# MCU.net
KiCad netlist of a schematic drawn in Altium Designer
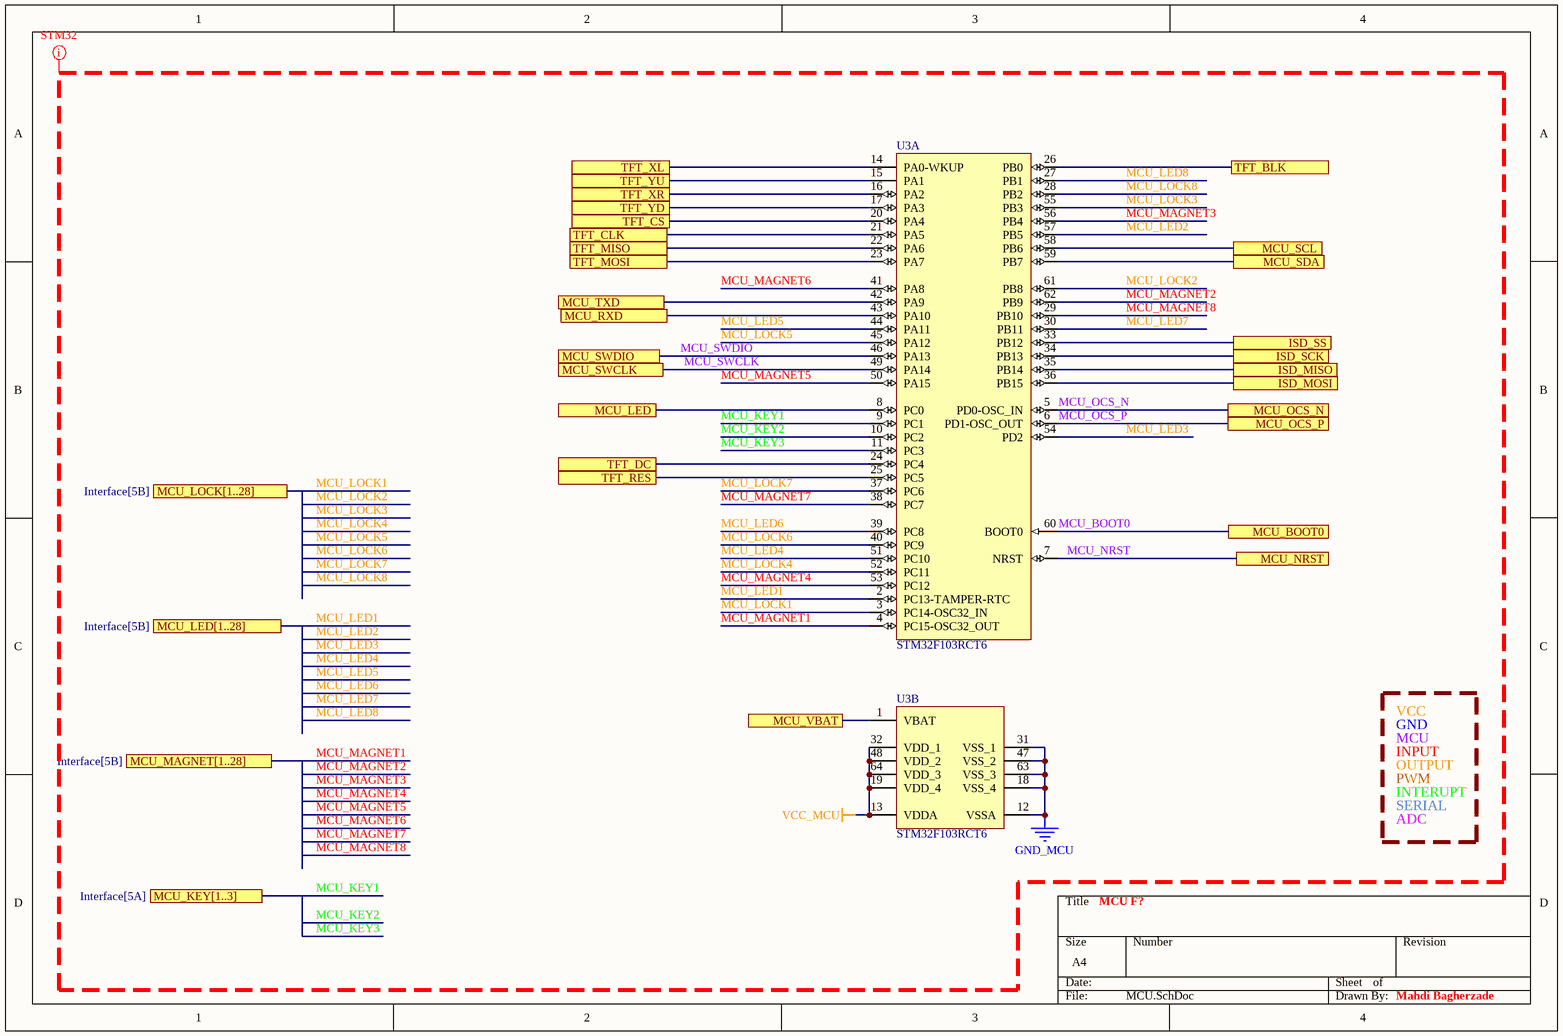
[diagram p0: MCU.SchDoc]

(export (version "E")
  (design (tool "Eeschema 10.0.6"))
  (components
    (comp (ref "U3")
      (value "STM32F103RCT6")
      (footprint "STM-LQFP64_N")
      (libsource (lib "ST Microelectronics STM32 F1") (part "STM32F103RCT6"))
    )
  )
  (nets
    (net (code "61") (name "/ISD_MISO") (class "Default")
      (node (ref "U3") (pin "35") (pinfunction "PB14_35") (pintype "bidirectional"))
    )
    (net (code "62") (name "/ISD_MOSI") (class "Default")
      (node (ref "U3") (pin "36") (pinfunction "PB15_36") (pintype "bidirectional"))
    )
    (net (code "63") (name "/ISD_SCK") (class "Default")
      (node (ref "U3") (pin "34") (pinfunction "PB13_34") (pintype "bidirectional"))
    )
    (net (code "64") (name "/ISD_SS") (class "Default")
      (node (ref "U3") (pin "33") (pinfunction "PB12_33") (pintype "bidirectional"))
    )
    (net (code "65") (name "/MCU_BOOT0") (class "Default")
      (node (ref "U3") (pin "60") (pinfunction "BOOT0_60") (pintype "input"))
    )
    (net (code "66") (name "/MCU_KEY1") (class "Default")
      (node (ref "U3") (pin "9") (pinfunction "PC1_9") (pintype "bidirectional"))
    )
    (net (code "67") (name "/MCU_KEY2") (class "Default")
      (node (ref "U3") (pin "10") (pinfunction "PC2_10") (pintype "bidirectional"))
    )
    (net (code "68") (name "/MCU_KEY3") (class "Default")
      (node (ref "U3") (pin "11") (pinfunction "PC3_11") (pintype "bidirectional"))
    )
    (net (code "70") (name "/MCU_LED") (class "Default")
      (node (ref "U3") (pin "8") (pinfunction "PC0_8") (pintype "bidirectional"))
    )
    (net (code "71") (name "/MCU_LED1") (class "Default")
      (node (ref "U3") (pin "2") (pinfunction "PC13-TAMPER-RTC_2") (pintype "bidirectional"))
    )
    (net (code "72") (name "/MCU_LED2") (class "Default")
      (node (ref "U3") (pin "57") (pinfunction "PB5_57") (pintype "bidirectional"))
    )
    (net (code "73") (name "/MCU_LED3") (class "Default")
      (node (ref "U3") (pin "54") (pinfunction "PD2_54") (pintype "bidirectional"))
    )
    (net (code "74") (name "/MCU_LED4") (class "Default")
      (node (ref "U3") (pin "51") (pinfunction "PC10_51") (pintype "bidirectional"))
    )
    (net (code "75") (name "/MCU_LED5") (class "Default")
      (node (ref "U3") (pin "44") (pinfunction "PA11_44") (pintype "bidirectional"))
    )
    (net (code "76") (name "/MCU_LED6") (class "Default")
      (node (ref "U3") (pin "39") (pinfunction "PC8_39") (pintype "bidirectional"))
    )
    (net (code "77") (name "/MCU_LED7") (class "Default")
      (node (ref "U3") (pin "30") (pinfunction "PB11_30") (pintype "bidirectional"))
    )
    (net (code "78") (name "/MCU_LED8") (class "Default")
      (node (ref "U3") (pin "27") (pinfunction "PB1_27") (pintype "bidirectional"))
    )
    (net (code "80") (name "/MCU_LOCK1") (class "Default")
      (node (ref "U3") (pin "3") (pinfunction "PC14-OSC32_IN_3") (pintype "bidirectional"))
    )
    (net (code "81") (name "/MCU_LOCK2") (class "Default")
      (node (ref "U3") (pin "61") (pinfunction "PB8_61") (pintype "bidirectional"))
    )
    (net (code "82") (name "/MCU_LOCK3") (class "Default")
      (node (ref "U3") (pin "55") (pinfunction "PB3_55") (pintype "bidirectional"))
    )
    (net (code "83") (name "/MCU_LOCK4") (class "Default")
      (node (ref "U3") (pin "52") (pinfunction "PC11_52") (pintype "bidirectional"))
    )
    (net (code "84") (name "/MCU_LOCK5") (class "Default")
      (node (ref "U3") (pin "45") (pinfunction "PA12_45") (pintype "bidirectional"))
    )
    (net (code "85") (name "/MCU_LOCK6") (class "Default")
      (node (ref "U3") (pin "40") (pinfunction "PC9_40") (pintype "bidirectional"))
    )
    (net (code "86") (name "/MCU_LOCK7") (class "Default")
      (node (ref "U3") (pin "37") (pinfunction "PC6_37") (pintype "bidirectional"))
    )
    (net (code "87") (name "/MCU_LOCK8") (class "Default")
      (node (ref "U3") (pin "28") (pinfunction "PB2_28") (pintype "bidirectional"))
    )
    (net (code "89") (name "/MCU_MAGNET1") (class "Default")
      (node (ref "U3") (pin "4") (pinfunction "PC15-OSC32_OUT_4") (pintype "bidirectional"))
    )
    (net (code "90") (name "/MCU_MAGNET2") (class "Default")
      (node (ref "U3") (pin "62") (pinfunction "PB9_62") (pintype "bidirectional"))
    )
    (net (code "91") (name "/MCU_MAGNET3") (class "Default")
      (node (ref "U3") (pin "56") (pinfunction "PB4_56") (pintype "bidirectional"))
    )
    (net (code "92") (name "/MCU_MAGNET4") (class "Default")
      (node (ref "U3") (pin "53") (pinfunction "PC12_53") (pintype "bidirectional"))
    )
    (net (code "93") (name "/MCU_MAGNET5") (class "Default")
      (node (ref "U3") (pin "50") (pinfunction "PA15_50") (pintype "bidirectional"))
    )
    (net (code "94") (name "/MCU_MAGNET6") (class "Default")
      (node (ref "U3") (pin "41") (pinfunction "PA8_41") (pintype "bidirectional"))
    )
    (net (code "95") (name "/MCU_MAGNET7") (class "Default")
      (node (ref "U3") (pin "38") (pinfunction "PC7_38") (pintype "bidirectional"))
    )
    (net (code "96") (name "/MCU_MAGNET8") (class "Default")
      (node (ref "U3") (pin "29") (pinfunction "PB10_29") (pintype "bidirectional"))
    )
    (net (code "98") (name "/MCU_NRST") (class "Default")
      (node (ref "U3") (pin "7") (pinfunction "NRST_7") (pintype "bidirectional"))
    )
    (net (code "99") (name "/MCU_OCS_N") (class "Default")
      (node (ref "U3") (pin "5") (pinfunction "PD0-OSC_IN_5") (pintype "bidirectional"))
    )
    (net (code "100") (name "/MCU_OCS_P") (class "Default")
      (node (ref "U3") (pin "6") (pinfunction "PD1-OSC_OUT_6") (pintype "bidirectional"))
    )
    (net (code "101") (name "/MCU_RXD") (class "Default")
      (node (ref "U3") (pin "43") (pinfunction "PA10_43") (pintype "bidirectional"))
    )
    (net (code "102") (name "/MCU_SCL") (class "Default")
      (node (ref "U3") (pin "58") (pinfunction "PB6_58") (pintype "bidirectional"))
    )
    (net (code "103") (name "/MCU_SDA") (class "Default")
      (node (ref "U3") (pin "59") (pinfunction "PB7_59") (pintype "bidirectional"))
    )
    (net (code "104") (name "/MCU_SWCLK") (class "Default")
      (node (ref "U3") (pin "49") (pinfunction "PA14_49") (pintype "bidirectional"))
    )
    (net (code "105") (name "/MCU_SWDIO") (class "Default")
      (node (ref "U3") (pin "46") (pinfunction "PA13_46") (pintype "bidirectional"))
    )
    (net (code "106") (name "/MCU_TXD") (class "Default")
      (node (ref "U3") (pin "42") (pinfunction "PA9_42") (pintype "bidirectional"))
    )
    (net (code "107") (name "/MCU_VBAT") (class "Default")
      (node (ref "U3") (pin "1") (pinfunction "VBAT_1") (pintype "power_in"))
    )
    (net (code "108") (name "/TFT_BLK") (class "Default")
      (node (ref "U3") (pin "26") (pinfunction "PB0_26") (pintype "bidirectional"))
    )
    (net (code "109") (name "/TFT_CLK") (class "Default")
      (node (ref "U3") (pin "21") (pinfunction "PA5_21") (pintype "bidirectional"))
    )
    (net (code "110") (name "/TFT_CS") (class "Default")
      (node (ref "U3") (pin "20") (pinfunction "PA4_20") (pintype "bidirectional"))
    )
    (net (code "111") (name "/TFT_DC") (class "Default")
      (node (ref "U3") (pin "24") (pinfunction "PC4_24") (pintype "bidirectional"))
    )
    (net (code "112") (name "/TFT_MISO") (class "Default")
      (node (ref "U3") (pin "22") (pinfunction "PA6_22") (pintype "bidirectional"))
    )
    (net (code "113") (name "/TFT_MOSI") (class "Default")
      (node (ref "U3") (pin "23") (pinfunction "PA7_23") (pintype "bidirectional"))
    )
    (net (code "114") (name "/TFT_RES") (class "Default")
      (node (ref "U3") (pin "25") (pinfunction "PC5_25") (pintype "bidirectional"))
    )
    (net (code "115") (name "/TFT_XL") (class "Default")
      (node (ref "U3") (pin "14") (pinfunction "PA0-WKUP_14") (pintype "passive"))
    )
    (net (code "116") (name "/TFT_XR") (class "Default")
      (node (ref "U3") (pin "16") (pinfunction "PA2_16") (pintype "bidirectional"))
    )
    (net (code "117") (name "/TFT_YD") (class "Default")
      (node (ref "U3") (pin "17") (pinfunction "PA3_17") (pintype "bidirectional"))
    )
    (net (code "118") (name "/TFT_YU") (class "Default")
      (node (ref "U3") (pin "15") (pinfunction "PA1_15") (pintype "passive"))
    )
    (net (code "119") (name "GND_MCU") (class "Default")
      (node (ref "U3") (pin "12") (pinfunction "VSSA_12") (pintype "power_in"))
      (node (ref "U3") (pin "18") (pinfunction "VSS_4_18") (pintype "power_in"))
      (node (ref "U3") (pin "31") (pinfunction "VSS_1_31") (pintype "power_in"))
      (node (ref "U3") (pin "47") (pinfunction "VSS_2_47") (pintype "power_in"))
      (node (ref "U3") (pin "63") (pinfunction "VSS_3_63") (pintype "power_in"))
    )
    (net (code "120") (name "VCC_MCU") (class "Default")
      (node (ref "U3") (pin "13") (pinfunction "VDDA_13") (pintype "power_in"))
      (node (ref "U3") (pin "19") (pinfunction "VDD_4_19") (pintype "power_in"))
      (node (ref "U3") (pin "32") (pinfunction "VDD_1_32") (pintype "power_in"))
      (node (ref "U3") (pin "48") (pinfunction "VDD_2_48") (pintype "power_in"))
      (node (ref "U3") (pin "64") (pinfunction "VDD_3_64") (pintype "power_in"))
    )
  )
)
